# Zio_Qwiic_MP3_Player.net
KiCad netlist of a schematic drawn in EAGLE
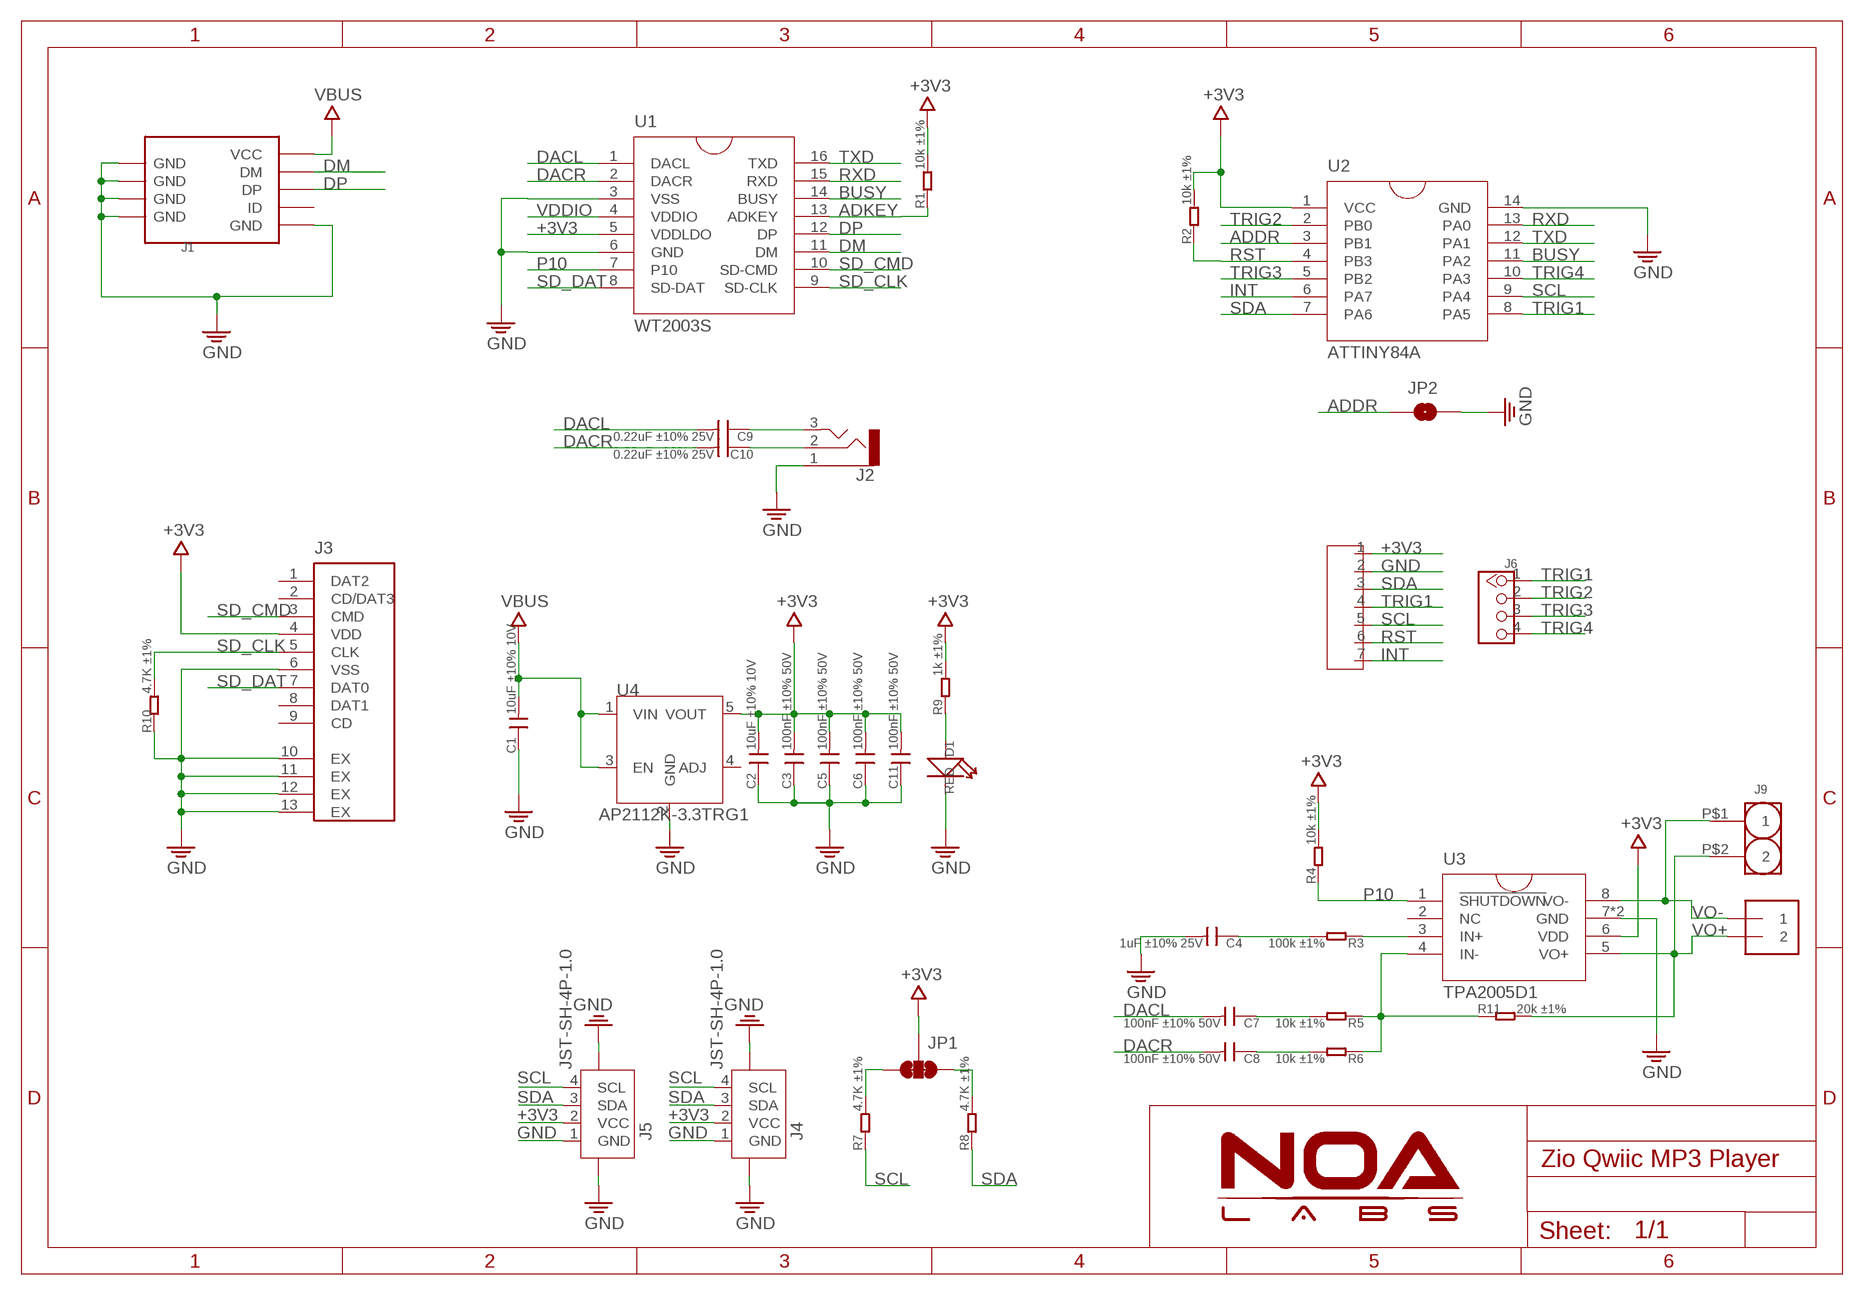
[diagram p0: schematic, sheet 1]

(export (version "E")
  (design (tool "Eeschema 10.0.6"))
  (components
    (comp (ref "C1")
      (value "10uF ±10% 10V")
      (footprint "eagle-import:C0603")
      (libsource (lib "eagle-import") (part "C-0603"))
    )
    (comp (ref "C2")
      (value "10uF ±10% 10V")
      (footprint "eagle-import:C0603")
      (libsource (lib "eagle-import") (part "C-0603"))
    )
    (comp (ref "C3")
      (value "100nF ±10% 50V")
      (footprint "eagle-import:C0603")
      (libsource (lib "eagle-import") (part "C-0603"))
    )
    (comp (ref "C4")
      (value "1uF ±10% 25V")
      (footprint "eagle-import:C0603")
      (libsource (lib "eagle-import") (part "C-0603"))
    )
    (comp (ref "C5")
      (value "100nF ±10% 50V")
      (footprint "eagle-import:C0603")
      (libsource (lib "eagle-import") (part "C-0603"))
    )
    (comp (ref "C6")
      (value "100nF ±10% 50V")
      (footprint "eagle-import:C0603")
      (libsource (lib "eagle-import") (part "C-0603"))
    )
    (comp (ref "C7")
      (value "100nF ±10% 50V")
      (footprint "eagle-import:C0603")
      (libsource (lib "eagle-import") (part "C-0603"))
    )
    (comp (ref "C8")
      (value "100nF ±10% 50V")
      (footprint "eagle-import:C0603")
      (libsource (lib "eagle-import") (part "C-0603"))
    )
    (comp (ref "C9")
      (value "0.22uF ±10% 25V")
      (footprint "eagle-import:C0603")
      (libsource (lib "eagle-import") (part "C-0603"))
    )
    (comp (ref "C10")
      (value "0.22uF ±10% 25V")
      (footprint "eagle-import:C0603")
      (libsource (lib "eagle-import") (part "C-0603"))
    )
    (comp (ref "C11")
      (value "100nF ±10% 50V")
      (footprint "eagle-import:C0603")
      (libsource (lib "eagle-import") (part "C-0603"))
    )
    (comp (ref "D1")
      (value "RED")
      (footprint "eagle-import:LED-0603")
      (libsource (lib "eagle-import") (part "LED'0603'"))
    )
    (comp (ref "J1")
      (value "USB-MICROE")
      (footprint "eagle-import:MICRO-SMD")
      (libsource (lib "eagle-import") (part "USB-MICROE"))
    )
    (comp (ref "J2")
      (value "AUDIO-3PPJ-320B")
      (footprint "eagle-import:3P-SMD-3.5MM")
      (libsource (lib "eagle-import") (part "AUDIO-3PPJ-320B"))
    )
    (comp (ref "J3")
      (value "TF_CARD")
      (footprint "eagle-import:TF_CARD")
      (libsource (lib "eagle-import") (part "TF_CARD"))
    )
    (comp (ref "J4")
      (value "JST-SH-4P-1.0")
      (footprint "eagle-import:JST-SH-4P")
      (libsource (lib "eagle-import") (part "JST-SH-4P-1.0"))
    )
    (comp (ref "J5")
      (value "JST-SH-4P-1.0")
      (footprint "eagle-import:JST-SH-4P")
      (libsource (lib "eagle-import") (part "JST-SH-4P-1.0"))
    )
    (comp (ref "J6")
      (value "HEADER-4P-60/35MIL")
      (footprint "eagle-import:4P-65_35MIL")
      (libsource (lib "eagle-import") (part "HEADER-4P-60/35MIL"))
    )
    (comp (ref "J7")
      (value "HEADER-7P")
      (footprint "eagle-import:7P-2.54-60_35MIL")
      (libsource (lib "eagle-import") (part "HEADER-7P"))
    )
    (comp (ref "J8")
      (value "TERMBLOCK_1X2-3.5MM")
      (footprint "eagle-import:1X2-3.5MM")
      (libsource (lib "eagle-import") (part "TERMBLOCK_1X2-3.5MM"))
    )
    (comp (ref "J9")
      (value "HEADER-2P")
      (footprint "eagle-import:插片")
      (libsource (lib "eagle-import") (part "HEADER-2P"))
    )
    (comp (ref "JP1")
      (value "SMT-JUMPER_3_2-NC_TRACE")
      (footprint "eagle-import:SMT-JUMPER_3_2-NC_TRACE")
      (libsource (lib "eagle-import") (part "SMT-JUMPER_3_2-NC_TRACE"))
    )
    (comp (ref "JP2")
      (value "JUMPER-SMT_2_NC_PASTE_NOCREM")
      (footprint "eagle-import:SMT-JUMPER_2_NC_PASTE_SILK_NOCREM")
      (libsource (lib "eagle-import") (part "JUMPER-SMT_2_NC_PASTE_NOCREM"))
    )
    (comp (ref "R1")
      (value "10k ±1%")
      (footprint "eagle-import:R0603")
      (libsource (lib "eagle-import") (part "R-0603"))
    )
    (comp (ref "R2")
      (value "10k ±1%")
      (footprint "eagle-import:R0603")
      (libsource (lib "eagle-import") (part "R-0603"))
    )
    (comp (ref "R3")
      (value "100k ±1%")
      (footprint "eagle-import:R0603")
      (libsource (lib "eagle-import") (part "R-0603"))
    )
    (comp (ref "R4")
      (value "10k ±1%")
      (footprint "eagle-import:R0603")
      (libsource (lib "eagle-import") (part "R-0603"))
    )
    (comp (ref "R5")
      (value "10k ±1%")
      (footprint "eagle-import:R0603")
      (libsource (lib "eagle-import") (part "R-0603"))
    )
    (comp (ref "R6")
      (value "10k ±1%")
      (footprint "eagle-import:R0603")
      (libsource (lib "eagle-import") (part "R-0603"))
    )
    (comp (ref "R7")
      (value "4.7K ±1%")
      (footprint "eagle-import:R0603")
      (libsource (lib "eagle-import") (part "R-0603"))
    )
    (comp (ref "R8")
      (value "4.7K ±1%")
      (footprint "eagle-import:R0603")
      (libsource (lib "eagle-import") (part "R-0603"))
    )
    (comp (ref "R9")
      (value "1k ±1%")
      (footprint "eagle-import:R0603")
      (libsource (lib "eagle-import") (part "R-0603"))
    )
    (comp (ref "R10")
      (value "4.7K ±1%")
      (footprint "eagle-import:R0603")
      (libsource (lib "eagle-import") (part "R-0603"))
    )
    (comp (ref "R11")
      (value "20k ±1%")
      (footprint "eagle-import:R0603")
      (libsource (lib "eagle-import") (part "R-0603"))
    )
    (comp (ref "U1")
      (value "WT2003S")
      (footprint "eagle-import:SO16")
      (libsource (lib "eagle-import") (part "WT2003S"))
    )
    (comp (ref "U2")
      (value "ATTINY84A")
      (footprint "eagle-import:SO14")
      (libsource (lib "eagle-import") (part "ATTINY84A"))
    )
    (comp (ref "U3")
      (value "TPA2005D1")
      (footprint "eagle-import:MSOP-8")
      (libsource (lib "eagle-import") (part "TPA2005D1POWERPAD"))
    )
    (comp (ref "U4")
      (value "AP2112K-3.3TRG1")
      (footprint "eagle-import:SOT23-5")
      (libsource (lib "eagle-import") (part "AP2112"))
    )
  )
  (nets
    (net (code "1") (name "+3V3") (class "Default")
      (node (ref "C11") (pin "2") (pinfunction "2_2") (pintype "passive"))
      (node (ref "C2") (pin "2") (pinfunction "2_2") (pintype "passive"))
      (node (ref "C3") (pin "2") (pinfunction "2_2") (pintype "passive"))
      (node (ref "C5") (pin "2") (pinfunction "2_2") (pintype "passive"))
      (node (ref "C6") (pin "2") (pinfunction "2_2") (pintype "passive"))
      (node (ref "J3") (pin "4") (pinfunction "VDD_4") (pintype "bidirectional"))
      (node (ref "J4") (pin "2") (pinfunction "VCC_2") (pintype "bidirectional"))
      (node (ref "J5") (pin "2") (pinfunction "VCC_2") (pintype "bidirectional"))
      (node (ref "J7") (pin "1") (pinfunction "P$1_1") (pintype "bidirectional"))
      (node (ref "JP1") (pin "2") (pinfunction "2_2") (pintype "passive"))
      (node (ref "R1") (pin "2") (pinfunction "2_2") (pintype "passive"))
      (node (ref "R2") (pin "2") (pinfunction "2_2") (pintype "passive"))
      (node (ref "R4") (pin "2") (pinfunction "2_2") (pintype "passive"))
      (node (ref "R9") (pin "2") (pinfunction "2_2") (pintype "passive"))
      (node (ref "U1") (pin "5") (pinfunction "VDDLDO_5") (pintype "bidirectional"))
      (node (ref "U2") (pin "1") (pinfunction "VCC_1") (pintype "bidirectional"))
      (node (ref "U3") (pin "6") (pinfunction "VDD_6") (pintype "bidirectional"))
      (node (ref "U4") (pin "5") (pinfunction "VOUT_5") (pintype "bidirectional"))
    )
    (net (code "2") (name "/ADDR") (class "Default")
      (node (ref "JP2") (pin "1") (pinfunction "1_1") (pintype "passive"))
      (node (ref "U2") (pin "3") (pinfunction "PB1_3") (pintype "bidirectional"))
    )
    (net (code "3") (name "/ADKEY") (class "Default")
      (node (ref "R1") (pin "1") (pinfunction "1_1") (pintype "passive"))
      (node (ref "U1") (pin "13") (pinfunction "ADKEY_13") (pintype "bidirectional"))
    )
    (net (code "4") (name "/BUSY") (class "Default")
      (node (ref "U1") (pin "14") (pinfunction "BUSY_14") (pintype "bidirectional"))
      (node (ref "U2") (pin "11") (pinfunction "PA2_11") (pintype "bidirectional"))
    )
    (net (code "5") (name "/DACL") (class "Default")
      (node (ref "C7") (pin "2") (pinfunction "2_2") (pintype "passive"))
      (node (ref "C9") (pin "2") (pinfunction "2_2") (pintype "passive"))
      (node (ref "U1") (pin "1") (pinfunction "DACL_1") (pintype "bidirectional"))
    )
    (net (code "6") (name "/DACR") (class "Default")
      (node (ref "C10") (pin "2") (pinfunction "2_2") (pintype "passive"))
      (node (ref "C8") (pin "2") (pinfunction "2_2") (pintype "passive"))
      (node (ref "U1") (pin "2") (pinfunction "DACR_2") (pintype "bidirectional"))
    )
    (net (code "7") (name "/DM") (class "Default")
      (node (ref "J1") (pin "D-") (pinfunction "DM_D-") (pintype "bidirectional"))
      (node (ref "U1") (pin "11") (pinfunction "DM_11") (pintype "bidirectional"))
    )
    (net (code "8") (name "/DP") (class "Default")
      (node (ref "J1") (pin "D+") (pinfunction "DP_D+") (pintype "bidirectional"))
      (node (ref "U1") (pin "12") (pinfunction "DP_12") (pintype "bidirectional"))
    )
    (net (code "9") (name "/INT") (class "Default")
      (node (ref "J7") (pin "7") (pinfunction "P$7_7") (pintype "bidirectional"))
      (node (ref "U2") (pin "6") (pinfunction "PA7_6") (pintype "bidirectional"))
    )
    (net (code "10") (name "/P10") (class "Default")
      (node (ref "R4") (pin "1") (pinfunction "1_1") (pintype "passive"))
      (node (ref "U1") (pin "7") (pinfunction "P10_7") (pintype "bidirectional"))
      (node (ref "U3") (pin "1") (pinfunction "~{SHUTDOWN}_1") (pintype "bidirectional"))
    )
    (net (code "11") (name "/RST") (class "Default")
      (node (ref "J7") (pin "6") (pinfunction "P$6_6") (pintype "bidirectional"))
      (node (ref "R2") (pin "1") (pinfunction "1_1") (pintype "passive"))
      (node (ref "U2") (pin "4") (pinfunction "PB3_4") (pintype "bidirectional"))
    )
    (net (code "12") (name "/RXD") (class "Default")
      (node (ref "U1") (pin "15") (pinfunction "RXD_15") (pintype "bidirectional"))
      (node (ref "U2") (pin "13") (pinfunction "PA0_13") (pintype "bidirectional"))
    )
    (net (code "13") (name "/SCL") (class "Default")
      (node (ref "J4") (pin "4") (pinfunction "SCL_4") (pintype "bidirectional"))
      (node (ref "J5") (pin "4") (pinfunction "SCL_4") (pintype "bidirectional"))
      (node (ref "J7") (pin "5") (pinfunction "P$5_5") (pintype "bidirectional"))
      (node (ref "R7") (pin "1") (pinfunction "1_1") (pintype "passive"))
      (node (ref "U2") (pin "9") (pinfunction "PA4_9") (pintype "bidirectional"))
    )
    (net (code "14") (name "/SDA") (class "Default")
      (node (ref "J4") (pin "3") (pinfunction "SDA_3") (pintype "bidirectional"))
      (node (ref "J5") (pin "3") (pinfunction "SDA_3") (pintype "bidirectional"))
      (node (ref "J7") (pin "3") (pinfunction "P$3_3") (pintype "bidirectional"))
      (node (ref "R8") (pin "1") (pinfunction "1_1") (pintype "passive"))
      (node (ref "U2") (pin "7") (pinfunction "PA6_7") (pintype "bidirectional"))
    )
    (net (code "15") (name "/SD_CLK") (class "Default")
      (node (ref "J3") (pin "5") (pinfunction "CLK_5") (pintype "bidirectional"))
      (node (ref "R10") (pin "2") (pinfunction "2_2") (pintype "passive"))
      (node (ref "U1") (pin "9") (pinfunction "SD-CLK_9") (pintype "bidirectional"))
    )
    (net (code "16") (name "/SD_CMD") (class "Default")
      (node (ref "J3") (pin "3") (pinfunction "CMD_3") (pintype "bidirectional"))
      (node (ref "U1") (pin "10") (pinfunction "SD-CMD_10") (pintype "bidirectional"))
    )
    (net (code "17") (name "/SD_DAT") (class "Default")
      (node (ref "J3") (pin "7") (pinfunction "DAT0_7") (pintype "bidirectional"))
      (node (ref "U1") (pin "8") (pinfunction "SD-DAT_8") (pintype "bidirectional"))
    )
    (net (code "18") (name "/TRIG1") (class "Default")
      (node (ref "J6") (pin "1") (pinfunction "P$1_1") (pintype "bidirectional"))
      (node (ref "J7") (pin "4") (pinfunction "P$4_4") (pintype "bidirectional"))
      (node (ref "U2") (pin "8") (pinfunction "PA5_8") (pintype "bidirectional"))
    )
    (net (code "19") (name "/TRIG2") (class "Default")
      (node (ref "J6") (pin "2") (pinfunction "P$2_2") (pintype "bidirectional"))
      (node (ref "U2") (pin "2") (pinfunction "PB0_2") (pintype "bidirectional"))
    )
    (net (code "20") (name "/TRIG3") (class "Default")
      (node (ref "J6") (pin "3") (pinfunction "P$3_3") (pintype "bidirectional"))
      (node (ref "U2") (pin "5") (pinfunction "PB2_5") (pintype "bidirectional"))
    )
    (net (code "21") (name "/TRIG4") (class "Default")
      (node (ref "J6") (pin "4") (pinfunction "P$4_4") (pintype "bidirectional"))
      (node (ref "U2") (pin "10") (pinfunction "PA3_10") (pintype "bidirectional"))
    )
    (net (code "22") (name "/TXD") (class "Default")
      (node (ref "U1") (pin "16") (pinfunction "TXD_16") (pintype "bidirectional"))
      (node (ref "U2") (pin "12") (pinfunction "PA1_12") (pintype "bidirectional"))
    )
    (net (code "23") (name "/VDDIO") (class "Default")
      (node (ref "U1") (pin "4") (pinfunction "VDDIO_4") (pintype "bidirectional"))
    )
    (net (code "24") (name "/VO+") (class "Default")
      (node (ref "J8") (pin "2") (pinfunction "2_2") (pintype "passive"))
      (node (ref "J9") (pin "P$2") (pinfunction "2_P$2") (pintype "bidirectional"))
      (node (ref "R11") (pin "2") (pinfunction "2_2") (pintype "passive"))
      (node (ref "U3") (pin "5") (pinfunction "VO+_5") (pintype "bidirectional"))
    )
    (net (code "25") (name "/VO-") (class "Default")
      (node (ref "J8") (pin "1") (pinfunction "1_1") (pintype "passive"))
      (node (ref "J9") (pin "P$1") (pinfunction "1_P$1") (pintype "bidirectional"))
      (node (ref "U3") (pin "8") (pinfunction "VO-_8") (pintype "bidirectional"))
    )
    (net (code "26") (name "GND") (class "Default")
      (node (ref "C1") (pin "1") (pinfunction "1_1") (pintype "passive"))
      (node (ref "C11") (pin "1") (pinfunction "1_1") (pintype "passive"))
      (node (ref "C2") (pin "1") (pinfunction "1_1") (pintype "passive"))
      (node (ref "C3") (pin "1") (pinfunction "1_1") (pintype "passive"))
      (node (ref "C4") (pin "2") (pinfunction "2_2") (pintype "passive"))
      (node (ref "C5") (pin "1") (pinfunction "1_1") (pintype "passive"))
      (node (ref "C6") (pin "1") (pinfunction "1_1") (pintype "passive"))
      (node (ref "D1") (pin "-") (pinfunction "-_-") (pintype "passive"))
      (node (ref "J1") (pin "GND") (pinfunction "GND_GND") (pintype "bidirectional"))
      (node (ref "J1") (pin "S1") (pinfunction "GND_S1") (pintype "bidirectional"))
      (node (ref "J1") (pin "S1@1") (pinfunction "GND_S1@1") (pintype "bidirectional"))
      (node (ref "J1") (pin "S1@2") (pinfunction "GND_S1@2") (pintype "bidirectional"))
      (node (ref "J1") (pin "S2") (pinfunction "GND_S2") (pintype "bidirectional"))
      (node (ref "J1") (pin "S2@1") (pinfunction "GND_S2@1") (pintype "bidirectional"))
      (node (ref "J1") (pin "S2@2") (pinfunction "GND_S2@2") (pintype "bidirectional"))
      (node (ref "J1") (pin "S3") (pinfunction "GND_S3") (pintype "bidirectional"))
      (node (ref "J1") (pin "S3@1") (pinfunction "GND_S3@1") (pintype "bidirectional"))
      (node (ref "J1") (pin "S3@2") (pinfunction "GND_S3@2") (pintype "bidirectional"))
      (node (ref "J1") (pin "S4") (pinfunction "GND_S4") (pintype "bidirectional"))
      (node (ref "J1") (pin "S4@1") (pinfunction "GND_S4@1") (pintype "bidirectional"))
      (node (ref "J1") (pin "S4@2") (pinfunction "GND_S4@2") (pintype "bidirectional"))
      (node (ref "J1") (pin "S5") (pinfunction "GND_S5") (pintype "bidirectional"))
      (node (ref "J1") (pin "S6") (pinfunction "GND_S6") (pintype "bidirectional"))
      (node (ref "J2") (pin "1") (pinfunction "1_1") (pintype "bidirectional"))
      (node (ref "J3") (pin "10") (pinfunction "EX_10") (pintype "bidirectional"))
      (node (ref "J3") (pin "11") (pinfunction "EX_11") (pintype "bidirectional"))
      (node (ref "J3") (pin "12") (pinfunction "EX_12") (pintype "bidirectional"))
      (node (ref "J3") (pin "13") (pinfunction "EX_13") (pintype "bidirectional"))
      (node (ref "J3") (pin "6") (pinfunction "VSS_6") (pintype "bidirectional"))
      (node (ref "J4") (pin "1") (pinfunction "GND_1") (pintype "bidirectional"))
      (node (ref "J4") (pin "NC1") (pinfunction "5_NC1") (pintype "bidirectional"))
      (node (ref "J4") (pin "NC2") (pinfunction "6_NC2") (pintype "bidirectional"))
      (node (ref "J5") (pin "1") (pinfunction "GND_1") (pintype "bidirectional"))
      (node (ref "J5") (pin "NC1") (pinfunction "5_NC1") (pintype "bidirectional"))
      (node (ref "J5") (pin "NC2") (pinfunction "6_NC2") (pintype "bidirectional"))
      (node (ref "J7") (pin "2") (pinfunction "P$2_2") (pintype "bidirectional"))
      (node (ref "JP2") (pin "2") (pinfunction "2_2") (pintype "passive"))
      (node (ref "R10") (pin "1") (pinfunction "1_1") (pintype "passive"))
      (node (ref "U1") (pin "3") (pinfunction "VSS_3") (pintype "bidirectional"))
      (node (ref "U1") (pin "6") (pinfunction "GND_6") (pintype "bidirectional"))
      (node (ref "U2") (pin "14") (pinfunction "GND_14") (pintype "bidirectional"))
      (node (ref "U3") (pin "7") (pinfunction "GND_7") (pintype "bidirectional"))
      (node (ref "U3") (pin "9") (pinfunction "GND_9") (pintype "bidirectional"))
      (node (ref "U4") (pin "2") (pinfunction "GND_2") (pintype "bidirectional"))
    )
    (net (code "27") (name "Net-(C4-Pad1)") (class "Default")
      (node (ref "C4") (pin "1") (pinfunction "1_1") (pintype "passive"))
      (node (ref "R3") (pin "2") (pinfunction "2_2") (pintype "passive"))
    )
    (net (code "28") (name "Net-(C7-Pad1)") (class "Default")
      (node (ref "C7") (pin "1") (pinfunction "1_1") (pintype "passive"))
      (node (ref "R5") (pin "2") (pinfunction "2_2") (pintype "passive"))
    )
    (net (code "29") (name "Net-(C8-Pad1)") (class "Default")
      (node (ref "C8") (pin "1") (pinfunction "1_1") (pintype "passive"))
      (node (ref "R6") (pin "2") (pinfunction "2_2") (pintype "passive"))
    )
    (net (code "30") (name "Net-(C9-Pad1)") (class "Default")
      (node (ref "C9") (pin "1") (pinfunction "1_1") (pintype "passive"))
      (node (ref "J2") (pin "3") (pinfunction "3_3") (pintype "bidirectional"))
    )
    (net (code "31") (name "Net-(C10-Pad1)") (class "Default")
      (node (ref "C10") (pin "1") (pinfunction "1_1") (pintype "passive"))
      (node (ref "J2") (pin "2") (pinfunction "2_2") (pintype "bidirectional"))
    )
    (net (code "32") (name "Net-(D1-Pad+)") (class "Default")
      (node (ref "D1") (pin "+") (pinfunction "+_+") (pintype "passive"))
      (node (ref "R9") (pin "1") (pinfunction "1_1") (pintype "passive"))
    )
    (net (code "33") (name "Net-(JP1-Pad1)") (class "Default")
      (node (ref "JP1") (pin "1") (pinfunction "1_1") (pintype "passive"))
      (node (ref "R8") (pin "2") (pinfunction "2_2") (pintype "passive"))
    )
    (net (code "34") (name "Net-(JP1-Pad3)") (class "Default")
      (node (ref "JP1") (pin "3") (pinfunction "3_3") (pintype "passive"))
      (node (ref "R7") (pin "2") (pinfunction "2_2") (pintype "passive"))
    )
    (net (code "35") (name "Net-(U3-IN+)") (class "Default")
      (node (ref "R3") (pin "1") (pinfunction "1_1") (pintype "passive"))
      (node (ref "U3") (pin "3") (pinfunction "IN+_3") (pintype "bidirectional"))
    )
    (net (code "36") (name "Net-(U3-IN-)") (class "Default")
      (node (ref "R11") (pin "1") (pinfunction "1_1") (pintype "passive"))
      (node (ref "R5") (pin "1") (pinfunction "1_1") (pintype "passive"))
      (node (ref "R6") (pin "1") (pinfunction "1_1") (pintype "passive"))
      (node (ref "U3") (pin "4") (pinfunction "IN-_4") (pintype "bidirectional"))
    )
    (net (code "37") (name "VBUS") (class "Default")
      (node (ref "C1") (pin "2") (pinfunction "2_2") (pintype "passive"))
      (node (ref "J1") (pin "VBUS") (pinfunction "VCC_VBUS") (pintype "bidirectional"))
      (node (ref "U4") (pin "1") (pinfunction "VIN_1") (pintype "bidirectional"))
      (node (ref "U4") (pin "3") (pinfunction "EN_3") (pintype "bidirectional"))
    )
    (net (code "38") (name "unconnected-(J1-PadID)") (class "Default")
      (node (ref "J1") (pin "ID") (pinfunction "ID_ID") (pintype "bidirectional"))
    )
    (net (code "39") (name "unconnected-(J3-CD-Pad9)") (class "Default")
      (node (ref "J3") (pin "9") (pinfunction "CD_9") (pintype "bidirectional"))
    )
    (net (code "40") (name "unconnected-(J3-CD{slash}DAT3-Pad2)") (class "Default")
      (node (ref "J3") (pin "2") (pinfunction "CD/DAT3_2") (pintype "bidirectional"))
    )
    (net (code "41") (name "unconnected-(J3-DAT1-Pad8)") (class "Default")
      (node (ref "J3") (pin "8") (pinfunction "DAT1_8") (pintype "bidirectional"))
    )
    (net (code "42") (name "unconnected-(J3-DAT2-Pad1)") (class "Default")
      (node (ref "J3") (pin "1") (pinfunction "DAT2_1") (pintype "bidirectional"))
    )
    (net (code "43") (name "unconnected-(U3-NC-Pad2)") (class "Default")
      (node (ref "U3") (pin "2") (pinfunction "NC_2") (pintype "bidirectional"))
    )
    (net (code "44") (name "unconnected-(U4-ADJ-Pad4)") (class "Default")
      (node (ref "U4") (pin "4") (pinfunction "ADJ_4") (pintype "bidirectional"))
    )
  )
)
